# ESC.net
KiCad netlist of a schematic drawn in EAGLE
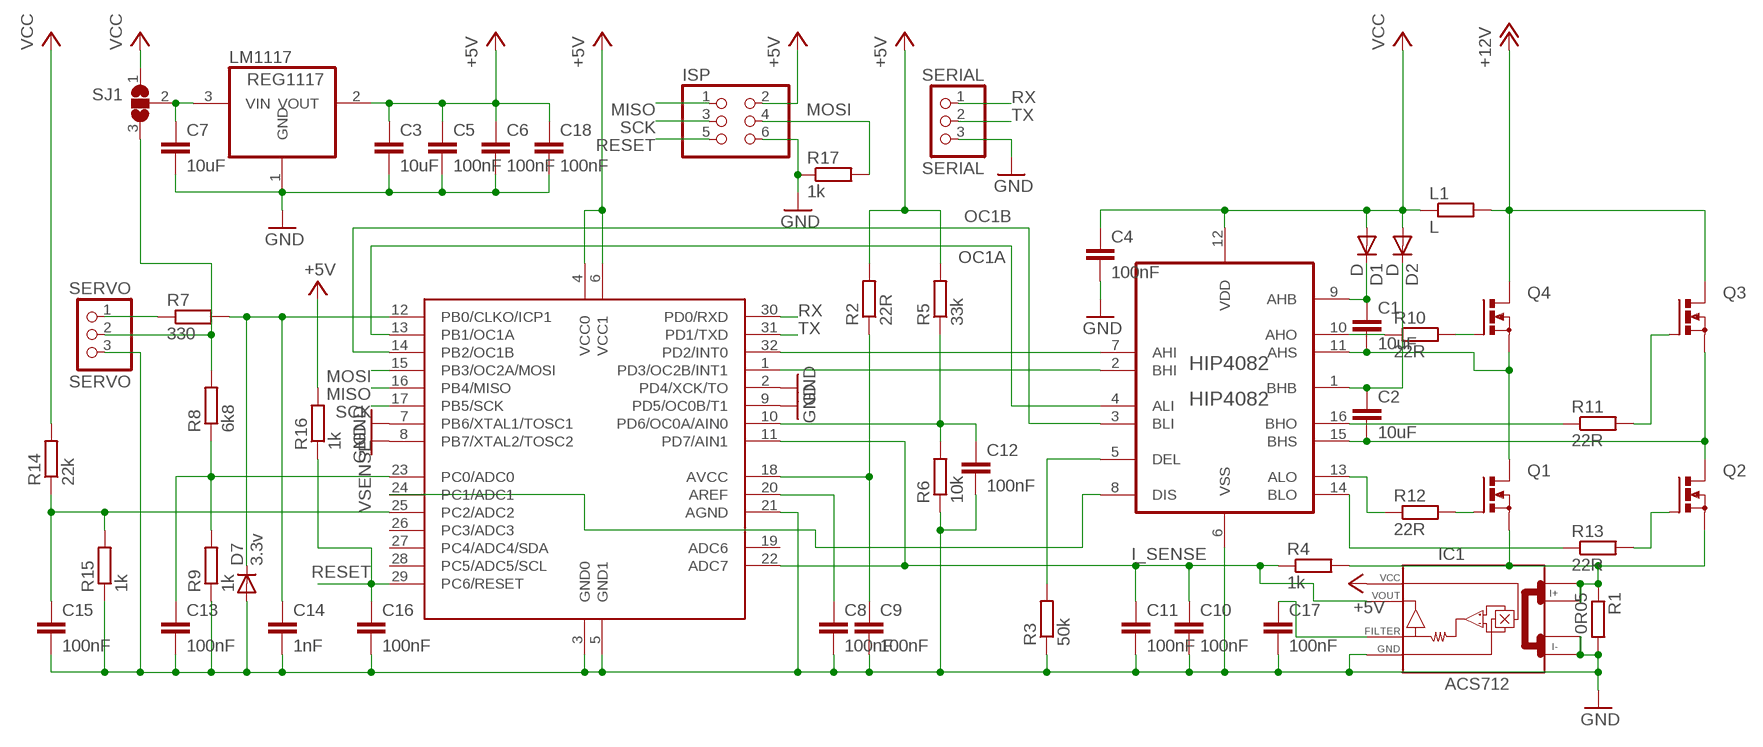
[diagram p0: schematic, sheet 1]

(export (version "E")
  (design (tool "Eeschema 10.0.6"))
  (components
    (comp (ref "ATMEGA328")
      (value "ATMEGA328")
      (footprint "eagle-import:MLF32")
      (libsource (lib "eagle-import") (part "ATMEGA48-88-168-328"))
    )
    (comp (ref "C1")
      (value "10uF")
      (footprint "eagle-import:C0805K")
      (libsource (lib "eagle-import") (part "C-EUC0805K"))
    )
    (comp (ref "C2")
      (value "10uF")
      (footprint "eagle-import:C0805K")
      (libsource (lib "eagle-import") (part "C-EUC0805K"))
    )
    (comp (ref "C3")
      (value "10uF")
      (footprint "eagle-import:C0805K")
      (libsource (lib "eagle-import") (part "C-EUC0805K"))
    )
    (comp (ref "C4")
      (value "100nF")
      (footprint "eagle-import:C0603K")
      (libsource (lib "eagle-import") (part "C-EUC0603K"))
    )
    (comp (ref "C5")
      (value "100nF")
      (footprint "eagle-import:C0603K")
      (libsource (lib "eagle-import") (part "C-EUC0603K"))
    )
    (comp (ref "C6")
      (value "100nF")
      (footprint "eagle-import:C0603K")
      (libsource (lib "eagle-import") (part "C-EUC0603K"))
    )
    (comp (ref "C7")
      (value "10uF")
      (footprint "eagle-import:C0805K")
      (libsource (lib "eagle-import") (part "C-EUC0805K"))
    )
    (comp (ref "C8")
      (value "100nF")
      (footprint "eagle-import:C0603K")
      (libsource (lib "eagle-import") (part "C-EUC0603K"))
    )
    (comp (ref "C9")
      (value "100nF")
      (footprint "eagle-import:C0603K")
      (libsource (lib "eagle-import") (part "C-EUC0603K"))
    )
    (comp (ref "C10")
      (value "100nF")
      (footprint "eagle-import:C0603K")
      (libsource (lib "eagle-import") (part "C-EUC0603K"))
    )
    (comp (ref "C11")
      (value "100nF")
      (footprint "eagle-import:C0603K")
      (libsource (lib "eagle-import") (part "C-EUC0603K"))
    )
    (comp (ref "C12")
      (value "100nF")
      (footprint "eagle-import:C0603K")
      (libsource (lib "eagle-import") (part "C-EUC0603K"))
    )
    (comp (ref "C13")
      (value "100nF")
      (footprint "eagle-import:C0603K")
      (libsource (lib "eagle-import") (part "C-EUC0603K"))
    )
    (comp (ref "C14")
      (value "1nF")
      (footprint "eagle-import:C0603K")
      (libsource (lib "eagle-import") (part "C-EUC0603K"))
    )
    (comp (ref "C15")
      (value "100nF")
      (footprint "eagle-import:C0603K")
      (libsource (lib "eagle-import") (part "C-EUC0603K"))
    )
    (comp (ref "C16")
      (value "100nF")
      (footprint "eagle-import:C0603K")
      (libsource (lib "eagle-import") (part "C-EUC0603K"))
    )
    (comp (ref "C17")
      (value "100nF")
      (footprint "eagle-import:C0603K")
      (libsource (lib "eagle-import") (part "C-EUC0603K"))
    )
    (comp (ref "C18")
      (value "100nF")
      (footprint "eagle-import:C0603K")
      (libsource (lib "eagle-import") (part "C-EUC0603K"))
    )
    (comp (ref "D1")
      (value "D")
      (footprint "eagle-import:SOD110-R")
      (libsource (lib "eagle-import") (part "DIODE-SOD110-R"))
    )
    (comp (ref "D2")
      (value "D")
      (footprint "eagle-import:SOD110-R")
      (libsource (lib "eagle-import") (part "DIODE-SOD110-R"))
    )
    (comp (ref "D7")
      (value "3.3v")
      (footprint "eagle-import:SOD-123_MINI-SMA")
      (libsource (lib "eagle-import") (part "CGRM400-G1"))
    )
    (comp (ref "HIP4082")
      (value "HIP4082")
      (footprint "eagle-import:SOIC127P600X175-16N")
      (fields (field (name "MPN") "HIP4082IBZ"))
      (libsource (lib "eagle-import") (part "HIP4082IBZ"))
    )
    (comp (ref "IC1")
      (value "ACS712")
      (footprint "eagle-import:SO08")
      (libsource (lib "eagle-import") (part "ACS712"))
    )
    (comp (ref "ISP")
      (value "PINHD-2X3")
      (footprint "eagle-import:2X03")
      (libsource (lib "eagle-import") (part "PINHD-2X3"))
    )
    (comp (ref "L1")
      (value "L")
      (footprint "eagle-import:M0805")
      (libsource (lib "eagle-import") (part "R-EU_M0805"))
    )
    (comp (ref "LM1117")
      (value "REG1117")
      (footprint "eagle-import:SOT223")
      (libsource (lib "eagle-import") (part "REG1117"))
    )
    (comp (ref "Q1")
      (value "PMOSFET_NTO220BV")
      (footprint "eagle-import:TO220BV")
      (libsource (lib "eagle-import") (part "PMOSFET_NTO220BV"))
    )
    (comp (ref "Q2")
      (value "PMOSFET_NTO220BV")
      (footprint "eagle-import:TO220BV")
      (libsource (lib "eagle-import") (part "PMOSFET_NTO220BV"))
    )
    (comp (ref "Q3")
      (value "PMOSFET_NTO220BV")
      (footprint "eagle-import:TO220BV")
      (libsource (lib "eagle-import") (part "PMOSFET_NTO220BV"))
    )
    (comp (ref "Q4")
      (value "PMOSFET_NTO220BV")
      (footprint "eagle-import:TO220BV")
      (libsource (lib "eagle-import") (part "PMOSFET_NTO220BV"))
    )
    (comp (ref "R1")
      (value "0R05")
      (footprint "eagle-import:R2512")
      (libsource (lib "eagle-import") (part "R-EU_R2512"))
    )
    (comp (ref "R2")
      (value "22R")
      (footprint "eagle-import:R0603")
      (libsource (lib "eagle-import") (part "R-EU_R0603"))
    )
    (comp (ref "R3")
      (value "50k")
      (footprint "eagle-import:R0603")
      (libsource (lib "eagle-import") (part "R-EU_R0603"))
    )
    (comp (ref "R4")
      (value "1k")
      (footprint "eagle-import:R0603")
      (libsource (lib "eagle-import") (part "R-EU_R0603"))
    )
    (comp (ref "R5")
      (value "33k")
      (footprint "eagle-import:R0603")
      (libsource (lib "eagle-import") (part "R-EU_R0603"))
    )
    (comp (ref "R6")
      (value "10k")
      (footprint "eagle-import:R0603")
      (libsource (lib "eagle-import") (part "R-EU_R0603"))
    )
    (comp (ref "R7")
      (value "330")
      (footprint "eagle-import:R0805")
      (libsource (lib "eagle-import") (part "R-EU_R0805"))
    )
    (comp (ref "R8")
      (value "6k8")
      (footprint "eagle-import:R0603")
      (libsource (lib "eagle-import") (part "R-EU_R0603"))
    )
    (comp (ref "R9")
      (value "1k")
      (footprint "eagle-import:R0603")
      (libsource (lib "eagle-import") (part "R-EU_R0603"))
    )
    (comp (ref "R10")
      (value "22R")
      (footprint "eagle-import:R0603")
      (libsource (lib "eagle-import") (part "R-EU_R0603"))
    )
    (comp (ref "R11")
      (value "22R")
      (footprint "eagle-import:R0603")
      (libsource (lib "eagle-import") (part "R-EU_R0603"))
    )
    (comp (ref "R12")
      (value "22R")
      (footprint "eagle-import:R0603")
      (libsource (lib "eagle-import") (part "R-EU_R0603"))
    )
    (comp (ref "R13")
      (value "22R")
      (footprint "eagle-import:R0603")
      (libsource (lib "eagle-import") (part "R-EU_R0603"))
    )
    (comp (ref "R14")
      (value "22k")
      (footprint "eagle-import:R0603")
      (libsource (lib "eagle-import") (part "R-EU_R0603"))
    )
    (comp (ref "R15")
      (value "1k")
      (footprint "eagle-import:R0603")
      (libsource (lib "eagle-import") (part "R-EU_R0603"))
    )
    (comp (ref "R16")
      (value "1k")
      (footprint "eagle-import:R0603")
      (libsource (lib "eagle-import") (part "R-EU_R0603"))
    )
    (comp (ref "R17")
      (value "1k")
      (footprint "eagle-import:R0603")
      (libsource (lib "eagle-import") (part "R-EU_R0603"))
    )
    (comp (ref "SERIAL")
      (value "SERIAL")
      (footprint "eagle-import:1X03")
      (libsource (lib "eagle-import") (part "PINHD-1X3"))
    )
    (comp (ref "SERVO")
      (value "SERVO")
      (footprint "eagle-import:1X03")
      (libsource (lib "eagle-import") (part "PINHD-1X3"))
    )
    (comp (ref "SJ1")
      (value "SJ2W")
      (footprint "eagle-import:SJ_2")
      (libsource (lib "eagle-import") (part "SJ2W"))
    )
  )
  (nets
    (net (code "1") (name "+5V") (class "Default")
      (node (ref "ATMEGA328") (pin "4") (pinfunction "VCC0_4") (pintype "power_in"))
      (node (ref "ATMEGA328") (pin "6") (pinfunction "VCC1_6") (pintype "power_in"))
      (node (ref "C18") (pin "1") (pinfunction "1_1") (pintype "passive"))
      (node (ref "C3") (pin "1") (pinfunction "1_1") (pintype "passive"))
      (node (ref "C5") (pin "1") (pinfunction "1_1") (pintype "passive"))
      (node (ref "C6") (pin "1") (pinfunction "1_1") (pintype "passive"))
      (node (ref "IC1") (pin "8") (pinfunction "VCC_8") (pintype "power_in"))
      (node (ref "ISP") (pin "2") (pinfunction "2_2") (pintype "passive"))
      (node (ref "LM1117") (pin "2") (pinfunction "VOUT_2") (pintype "output"))
      (node (ref "R16") (pin "2") (pinfunction "2_2") (pintype "passive"))
      (node (ref "R2") (pin "2") (pinfunction "2_2") (pintype "passive"))
      (node (ref "R5") (pin "2") (pinfunction "2_2") (pintype "passive"))
    )
    (net (code "2") (name "+12V") (class "Default")
      (node (ref "L1") (pin "2") (pinfunction "2_2") (pintype "passive"))
      (node (ref "Q3") (pin "D") (pinfunction "D_D") (pintype "passive"))
      (node (ref "Q4") (pin "D") (pinfunction "D_D") (pintype "passive"))
    )
    (net (code "3") (name "/I_SENSE") (class "Default")
      (node (ref "ATMEGA328") (pin "11") (pinfunction "PD7/AIN1_11") (pintype "bidirectional"))
      (node (ref "ATMEGA328") (pin "22") (pinfunction "ADC7_22") (pintype "input"))
      (node (ref "C10") (pin "1") (pinfunction "1_1") (pintype "passive"))
      (node (ref "C11") (pin "1") (pinfunction "1_1") (pintype "passive"))
      (node (ref "IC1") (pin "7") (pinfunction "VOUT_7") (pintype "output"))
      (node (ref "R4") (pin "1") (pinfunction "1_1") (pintype "passive"))
    )
    (net (code "4") (name "/MISO") (class "Default")
      (node (ref "ATMEGA328") (pin "16") (pinfunction "PB4/MISO_16") (pintype "bidirectional"))
      (node (ref "ISP") (pin "1") (pinfunction "1_1") (pintype "passive"))
    )
    (net (code "5") (name "/MOSI") (class "Default")
      (node (ref "ATMEGA328") (pin "15") (pinfunction "PB3/OC2A/MOSI_15") (pintype "bidirectional"))
      (node (ref "ISP") (pin "4") (pinfunction "4_4") (pintype "passive"))
      (node (ref "R17") (pin "2") (pinfunction "2_2") (pintype "passive"))
    )
    (net (code "6") (name "/OC1A") (class "Default")
      (node (ref "ATMEGA328") (pin "13") (pinfunction "PB1/OC1A_13") (pintype "bidirectional"))
      (node (ref "HIP4082") (pin "4") (pinfunction "ALI_4") (pintype "input"))
    )
    (net (code "7") (name "/OC1B") (class "Default")
      (node (ref "ATMEGA328") (pin "14") (pinfunction "PB2/OC1B_14") (pintype "bidirectional"))
      (node (ref "HIP4082") (pin "3") (pinfunction "BLI_3") (pintype "input"))
    )
    (net (code "8") (name "/RESET") (class "Default")
      (node (ref "ATMEGA328") (pin "29") (pinfunction "PC6/RESET_29") (pintype "bidirectional"))
      (node (ref "C16") (pin "1") (pinfunction "1_1") (pintype "passive"))
      (node (ref "ISP") (pin "5") (pinfunction "5_5") (pintype "passive"))
      (node (ref "R16") (pin "1") (pinfunction "1_1") (pintype "passive"))
    )
    (net (code "9") (name "/RX") (class "Default")
      (node (ref "ATMEGA328") (pin "30") (pinfunction "PD0/RXD_30") (pintype "bidirectional"))
      (node (ref "SERIAL") (pin "1") (pinfunction "1_1") (pintype "passive"))
    )
    (net (code "10") (name "/SCK") (class "Default")
      (node (ref "ATMEGA328") (pin "17") (pinfunction "PB5/SCK_17") (pintype "bidirectional"))
      (node (ref "ISP") (pin "3") (pinfunction "3_3") (pintype "passive"))
    )
    (net (code "11") (name "/TX") (class "Default")
      (node (ref "ATMEGA328") (pin "31") (pinfunction "PD1/TXD_31") (pintype "bidirectional"))
      (node (ref "SERIAL") (pin "2") (pinfunction "2_2") (pintype "passive"))
    )
    (net (code "12") (name "/VSENSE") (class "Default")
      (node (ref "ATMEGA328") (pin "25") (pinfunction "PC2/ADC2_25") (pintype "bidirectional"))
      (node (ref "C15") (pin "1") (pinfunction "1_1") (pintype "passive"))
      (node (ref "R14") (pin "1") (pinfunction "1_1") (pintype "passive"))
      (node (ref "R15") (pin "2") (pinfunction "2_2") (pintype "passive"))
    )
    (net (code "13") (name "GND") (class "Default")
      (node (ref "ATMEGA328") (pin "2") (pinfunction "PD4/XCK/TO_2") (pintype "bidirectional"))
      (node (ref "ATMEGA328") (pin "21") (pinfunction "AGND_21") (pintype "power_in"))
      (node (ref "ATMEGA328") (pin "3") (pinfunction "GND0_3") (pintype "power_in"))
      (node (ref "ATMEGA328") (pin "5") (pinfunction "GND1_5") (pintype "power_in"))
      (node (ref "ATMEGA328") (pin "7") (pinfunction "PB6/XTAL1/TOSC1_7") (pintype "bidirectional"))
      (node (ref "ATMEGA328") (pin "8") (pinfunction "PB7/XTAL2/TOSC2_8") (pintype "bidirectional"))
      (node (ref "ATMEGA328") (pin "9") (pinfunction "PD5/OC0B/T1_9") (pintype "bidirectional"))
      (node (ref "C10") (pin "2") (pinfunction "2_2") (pintype "passive"))
      (node (ref "C11") (pin "2") (pinfunction "2_2") (pintype "passive"))
      (node (ref "C12") (pin "2") (pinfunction "2_2") (pintype "passive"))
      (node (ref "C13") (pin "2") (pinfunction "2_2") (pintype "passive"))
      (node (ref "C14") (pin "2") (pinfunction "2_2") (pintype "passive"))
      (node (ref "C15") (pin "2") (pinfunction "2_2") (pintype "passive"))
      (node (ref "C16") (pin "2") (pinfunction "2_2") (pintype "passive"))
      (node (ref "C17") (pin "2") (pinfunction "2_2") (pintype "passive"))
      (node (ref "C18") (pin "2") (pinfunction "2_2") (pintype "passive"))
      (node (ref "C3") (pin "2") (pinfunction "2_2") (pintype "passive"))
      (node (ref "C4") (pin "2") (pinfunction "2_2") (pintype "passive"))
      (node (ref "C5") (pin "2") (pinfunction "2_2") (pintype "passive"))
      (node (ref "C6") (pin "2") (pinfunction "2_2") (pintype "passive"))
      (node (ref "C7") (pin "2") (pinfunction "2_2") (pintype "passive"))
      (node (ref "C8") (pin "2") (pinfunction "2_2") (pintype "passive"))
      (node (ref "C9") (pin "2") (pinfunction "2_2") (pintype "passive"))
      (node (ref "D7") (pin "A") (pinfunction "A_A") (pintype "passive"))
      (node (ref "HIP4082") (pin "6") (pinfunction "VSS_6") (pintype "input"))
      (node (ref "IC1") (pin "3") (pinfunction "I-_0_3") (pintype "bidirectional"))
      (node (ref "IC1") (pin "4") (pinfunction "I-_1_4") (pintype "bidirectional"))
      (node (ref "IC1") (pin "5") (pinfunction "GND_5") (pintype "power_in"))
      (node (ref "ISP") (pin "6") (pinfunction "6_6") (pintype "passive"))
      (node (ref "LM1117") (pin "1") (pinfunction "GND_1") (pintype "power_in"))
      (node (ref "R1") (pin "2") (pinfunction "2_2") (pintype "passive"))
      (node (ref "R15") (pin "1") (pinfunction "1_1") (pintype "passive"))
      (node (ref "R17") (pin "1") (pinfunction "1_1") (pintype "passive"))
      (node (ref "R3") (pin "1") (pinfunction "1_1") (pintype "passive"))
      (node (ref "R6") (pin "1") (pinfunction "1_1") (pintype "passive"))
      (node (ref "R9") (pin "1") (pinfunction "1_1") (pintype "passive"))
      (node (ref "SERIAL") (pin "3") (pinfunction "3_3") (pintype "passive"))
      (node (ref "SERVO") (pin "3") (pinfunction "3_3") (pintype "passive"))
    )
    (net (code "14") (name "Net-(ATMEGA328-AREF)") (class "Default")
      (node (ref "ATMEGA328") (pin "20") (pinfunction "AREF_20") (pintype "input"))
      (node (ref "C8") (pin "1") (pinfunction "1_1") (pintype "passive"))
    )
    (net (code "15") (name "Net-(ATMEGA328-AVCC)") (class "Default")
      (node (ref "ATMEGA328") (pin "18") (pinfunction "AVCC_18") (pintype "input"))
      (node (ref "C9") (pin "1") (pinfunction "1_1") (pintype "passive"))
      (node (ref "R2") (pin "1") (pinfunction "1_1") (pintype "passive"))
    )
    (net (code "16") (name "Net-(ATMEGA328-PB0{slash}CLKO{slash}ICP1)") (class "Default")
      (node (ref "ATMEGA328") (pin "12") (pinfunction "PB0/CLKO/ICP1_12") (pintype "bidirectional"))
      (node (ref "C14") (pin "1") (pinfunction "1_1") (pintype "passive"))
      (node (ref "D7") (pin "C") (pinfunction "C_C") (pintype "passive"))
      (node (ref "R7") (pin "2") (pinfunction "2_2") (pintype "passive"))
    )
    (net (code "17") (name "Net-(ATMEGA328-PC0{slash}ADC0)") (class "Default")
      (node (ref "ATMEGA328") (pin "23") (pinfunction "PC0/ADC0_23") (pintype "bidirectional"))
      (node (ref "C13") (pin "1") (pinfunction "1_1") (pintype "passive"))
      (node (ref "R8") (pin "1") (pinfunction "1_1") (pintype "passive"))
      (node (ref "R9") (pin "2") (pinfunction "2_2") (pintype "passive"))
    )
    (net (code "18") (name "Net-(ATMEGA328-PC1{slash}ADC1)") (class "Default")
      (node (ref "ATMEGA328") (pin "24") (pinfunction "PC1/ADC1_24") (pintype "bidirectional"))
      (node (ref "HIP4082") (pin "8") (pinfunction "DIS_8") (pintype "input"))
    )
    (net (code "19") (name "Net-(ATMEGA328-PD2{slash}INT0)") (class "Default")
      (node (ref "ATMEGA328") (pin "32") (pinfunction "PD2/INT0_32") (pintype "bidirectional"))
      (node (ref "HIP4082") (pin "7") (pinfunction "AHI_7") (pintype "input"))
    )
    (net (code "20") (name "Net-(ATMEGA328-PD3{slash}OC2B{slash}INT1)") (class "Default")
      (node (ref "ATMEGA328") (pin "1") (pinfunction "PD3/OC2B/INT1_1") (pintype "bidirectional"))
      (node (ref "HIP4082") (pin "2") (pinfunction "BHI_2") (pintype "input"))
    )
    (net (code "21") (name "Net-(ATMEGA328-PD6{slash}OC0A{slash}AIN0)") (class "Default")
      (node (ref "ATMEGA328") (pin "10") (pinfunction "PD6/OC0A/AIN0_10") (pintype "bidirectional"))
      (node (ref "C12") (pin "1") (pinfunction "1_1") (pintype "passive"))
      (node (ref "R5") (pin "1") (pinfunction "1_1") (pintype "passive"))
      (node (ref "R6") (pin "2") (pinfunction "2_2") (pintype "passive"))
    )
    (net (code "22") (name "Net-(HIP4082-AHB)") (class "Default")
      (node (ref "C1") (pin "1") (pinfunction "1_1") (pintype "passive"))
      (node (ref "D1") (pin "C") (pinfunction "C_C") (pintype "passive"))
      (node (ref "HIP4082") (pin "9") (pinfunction "AHB_9") (pintype "input"))
    )
    (net (code "23") (name "Net-(HIP4082-AHO)") (class "Default")
      (node (ref "HIP4082") (pin "10") (pinfunction "AHO_10") (pintype "output"))
      (node (ref "R10") (pin "1") (pinfunction "1_1") (pintype "passive"))
    )
    (net (code "24") (name "Net-(HIP4082-AHS)") (class "Default")
      (node (ref "C1") (pin "2") (pinfunction "2_2") (pintype "passive"))
      (node (ref "HIP4082") (pin "11") (pinfunction "AHS_11") (pintype "input"))
      (node (ref "Q1") (pin "D") (pinfunction "D_D") (pintype "passive"))
      (node (ref "Q4") (pin "S") (pinfunction "S_S") (pintype "passive"))
    )
    (net (code "25") (name "Net-(HIP4082-ALO)") (class "Default")
      (node (ref "HIP4082") (pin "13") (pinfunction "ALO_13") (pintype "output"))
      (node (ref "R12") (pin "1") (pinfunction "1_1") (pintype "passive"))
    )
    (net (code "26") (name "Net-(HIP4082-BHB)") (class "Default")
      (node (ref "C2") (pin "1") (pinfunction "1_1") (pintype "passive"))
      (node (ref "D2") (pin "C") (pinfunction "C_C") (pintype "passive"))
      (node (ref "HIP4082") (pin "1") (pinfunction "BHB_1") (pintype "input"))
    )
    (net (code "27") (name "Net-(HIP4082-BHO)") (class "Default")
      (node (ref "HIP4082") (pin "16") (pinfunction "BHO_16") (pintype "output"))
      (node (ref "R11") (pin "1") (pinfunction "1_1") (pintype "passive"))
    )
    (net (code "28") (name "Net-(HIP4082-BHS)") (class "Default")
      (node (ref "C2") (pin "2") (pinfunction "2_2") (pintype "passive"))
      (node (ref "HIP4082") (pin "15") (pinfunction "BHS_15") (pintype "input"))
      (node (ref "Q2") (pin "D") (pinfunction "D_D") (pintype "passive"))
      (node (ref "Q3") (pin "S") (pinfunction "S_S") (pintype "passive"))
    )
    (net (code "29") (name "Net-(HIP4082-BLO)") (class "Default")
      (node (ref "HIP4082") (pin "14") (pinfunction "BLO_14") (pintype "output"))
      (node (ref "R13") (pin "1") (pinfunction "1_1") (pintype "passive"))
    )
    (net (code "30") (name "Net-(HIP4082-DEL)") (class "Default")
      (node (ref "HIP4082") (pin "5") (pinfunction "DEL_5") (pintype "input"))
      (node (ref "R3") (pin "2") (pinfunction "2_2") (pintype "passive"))
    )
    (net (code "31") (name "Net-(IC1-FILTER)") (class "Default")
      (node (ref "C17") (pin "1") (pinfunction "1_1") (pintype "passive"))
      (node (ref "IC1") (pin "6") (pinfunction "FILTER_6") (pintype "bidirectional"))
    )
    (net (code "32") (name "Net-(IC1-I+_0)") (class "Default")
      (node (ref "IC1") (pin "1") (pinfunction "I+_0_1") (pintype "bidirectional"))
      (node (ref "IC1") (pin "2") (pinfunction "I+_1_2") (pintype "bidirectional"))
      (node (ref "Q1") (pin "S") (pinfunction "S_S") (pintype "passive"))
      (node (ref "Q2") (pin "S") (pinfunction "S_S") (pintype "passive"))
      (node (ref "R1") (pin "1") (pinfunction "1_1") (pintype "passive"))
      (node (ref "R4") (pin "2") (pinfunction "2_2") (pintype "passive"))
    )
    (net (code "33") (name "Net-(LM1117-VIN)") (class "Default")
      (node (ref "C7") (pin "1") (pinfunction "1_1") (pintype "passive"))
      (node (ref "LM1117") (pin "3") (pinfunction "VIN_3") (pintype "input"))
      (node (ref "SJ1") (pin "2") (pinfunction "2_2") (pintype "passive"))
    )
    (net (code "34") (name "Net-(Q1-PadG)") (class "Default")
      (node (ref "Q1") (pin "G") (pinfunction "G_G") (pintype "passive"))
      (node (ref "R12") (pin "2") (pinfunction "2_2") (pintype "passive"))
    )
    (net (code "35") (name "Net-(Q2-PadG)") (class "Default")
      (node (ref "Q2") (pin "G") (pinfunction "G_G") (pintype "passive"))
      (node (ref "R13") (pin "2") (pinfunction "2_2") (pintype "passive"))
    )
    (net (code "36") (name "Net-(Q3-PadG)") (class "Default")
      (node (ref "Q3") (pin "G") (pinfunction "G_G") (pintype "passive"))
      (node (ref "R11") (pin "2") (pinfunction "2_2") (pintype "passive"))
    )
    (net (code "37") (name "Net-(Q4-PadG)") (class "Default")
      (node (ref "Q4") (pin "G") (pinfunction "G_G") (pintype "passive"))
      (node (ref "R10") (pin "2") (pinfunction "2_2") (pintype "passive"))
    )
    (net (code "38") (name "Net-(R7-Pad1)") (class "Default")
      (node (ref "R7") (pin "1") (pinfunction "1_1") (pintype "passive"))
      (node (ref "SERVO") (pin "1") (pinfunction "1_1") (pintype "passive"))
    )
    (net (code "39") (name "Net-(R8-Pad2)") (class "Default")
      (node (ref "R8") (pin "2") (pinfunction "2_2") (pintype "passive"))
      (node (ref "SERVO") (pin "2") (pinfunction "2_2") (pintype "passive"))
      (node (ref "SJ1") (pin "3") (pinfunction "3_3") (pintype "passive"))
    )
    (net (code "40") (name "VCC") (class "Default")
      (node (ref "C4") (pin "1") (pinfunction "1_1") (pintype "passive"))
      (node (ref "D1") (pin "A") (pinfunction "A_A") (pintype "passive"))
      (node (ref "D2") (pin "A") (pinfunction "A_A") (pintype "passive"))
      (node (ref "HIP4082") (pin "12") (pinfunction "VDD_12") (pintype "input"))
      (node (ref "L1") (pin "1") (pinfunction "1_1") (pintype "passive"))
      (node (ref "R14") (pin "2") (pinfunction "2_2") (pintype "passive"))
      (node (ref "SJ1") (pin "1") (pinfunction "1_1") (pintype "passive"))
    )
    (net (code "41") (name "unconnected-(ATMEGA328-ADC6-Pad19)") (class "Default")
      (node (ref "ATMEGA328") (pin "19") (pinfunction "ADC6_19") (pintype "input"))
    )
    (net (code "42") (name "unconnected-(ATMEGA328-PC3{slash}ADC3-Pad26)") (class "Default")
      (node (ref "ATMEGA328") (pin "26") (pinfunction "PC3/ADC3_26") (pintype "bidirectional"))
    )
    (net (code "43") (name "unconnected-(ATMEGA328-PC4{slash}ADC4{slash}SDA-Pad27)") (class "Default")
      (node (ref "ATMEGA328") (pin "27") (pinfunction "PC4/ADC4/SDA_27") (pintype "bidirectional"))
    )
    (net (code "44") (name "unconnected-(ATMEGA328-PC5{slash}ADC5{slash}SCL-Pad28)") (class "Default")
      (node (ref "ATMEGA328") (pin "28") (pinfunction "PC5/ADC5/SCL_28") (pintype "bidirectional"))
    )
  )
)
